# JadePlus_v0_3_1_schematics_PG1_ESP32S3.net
KiCad netlist of a schematic drawn in Altium Designer
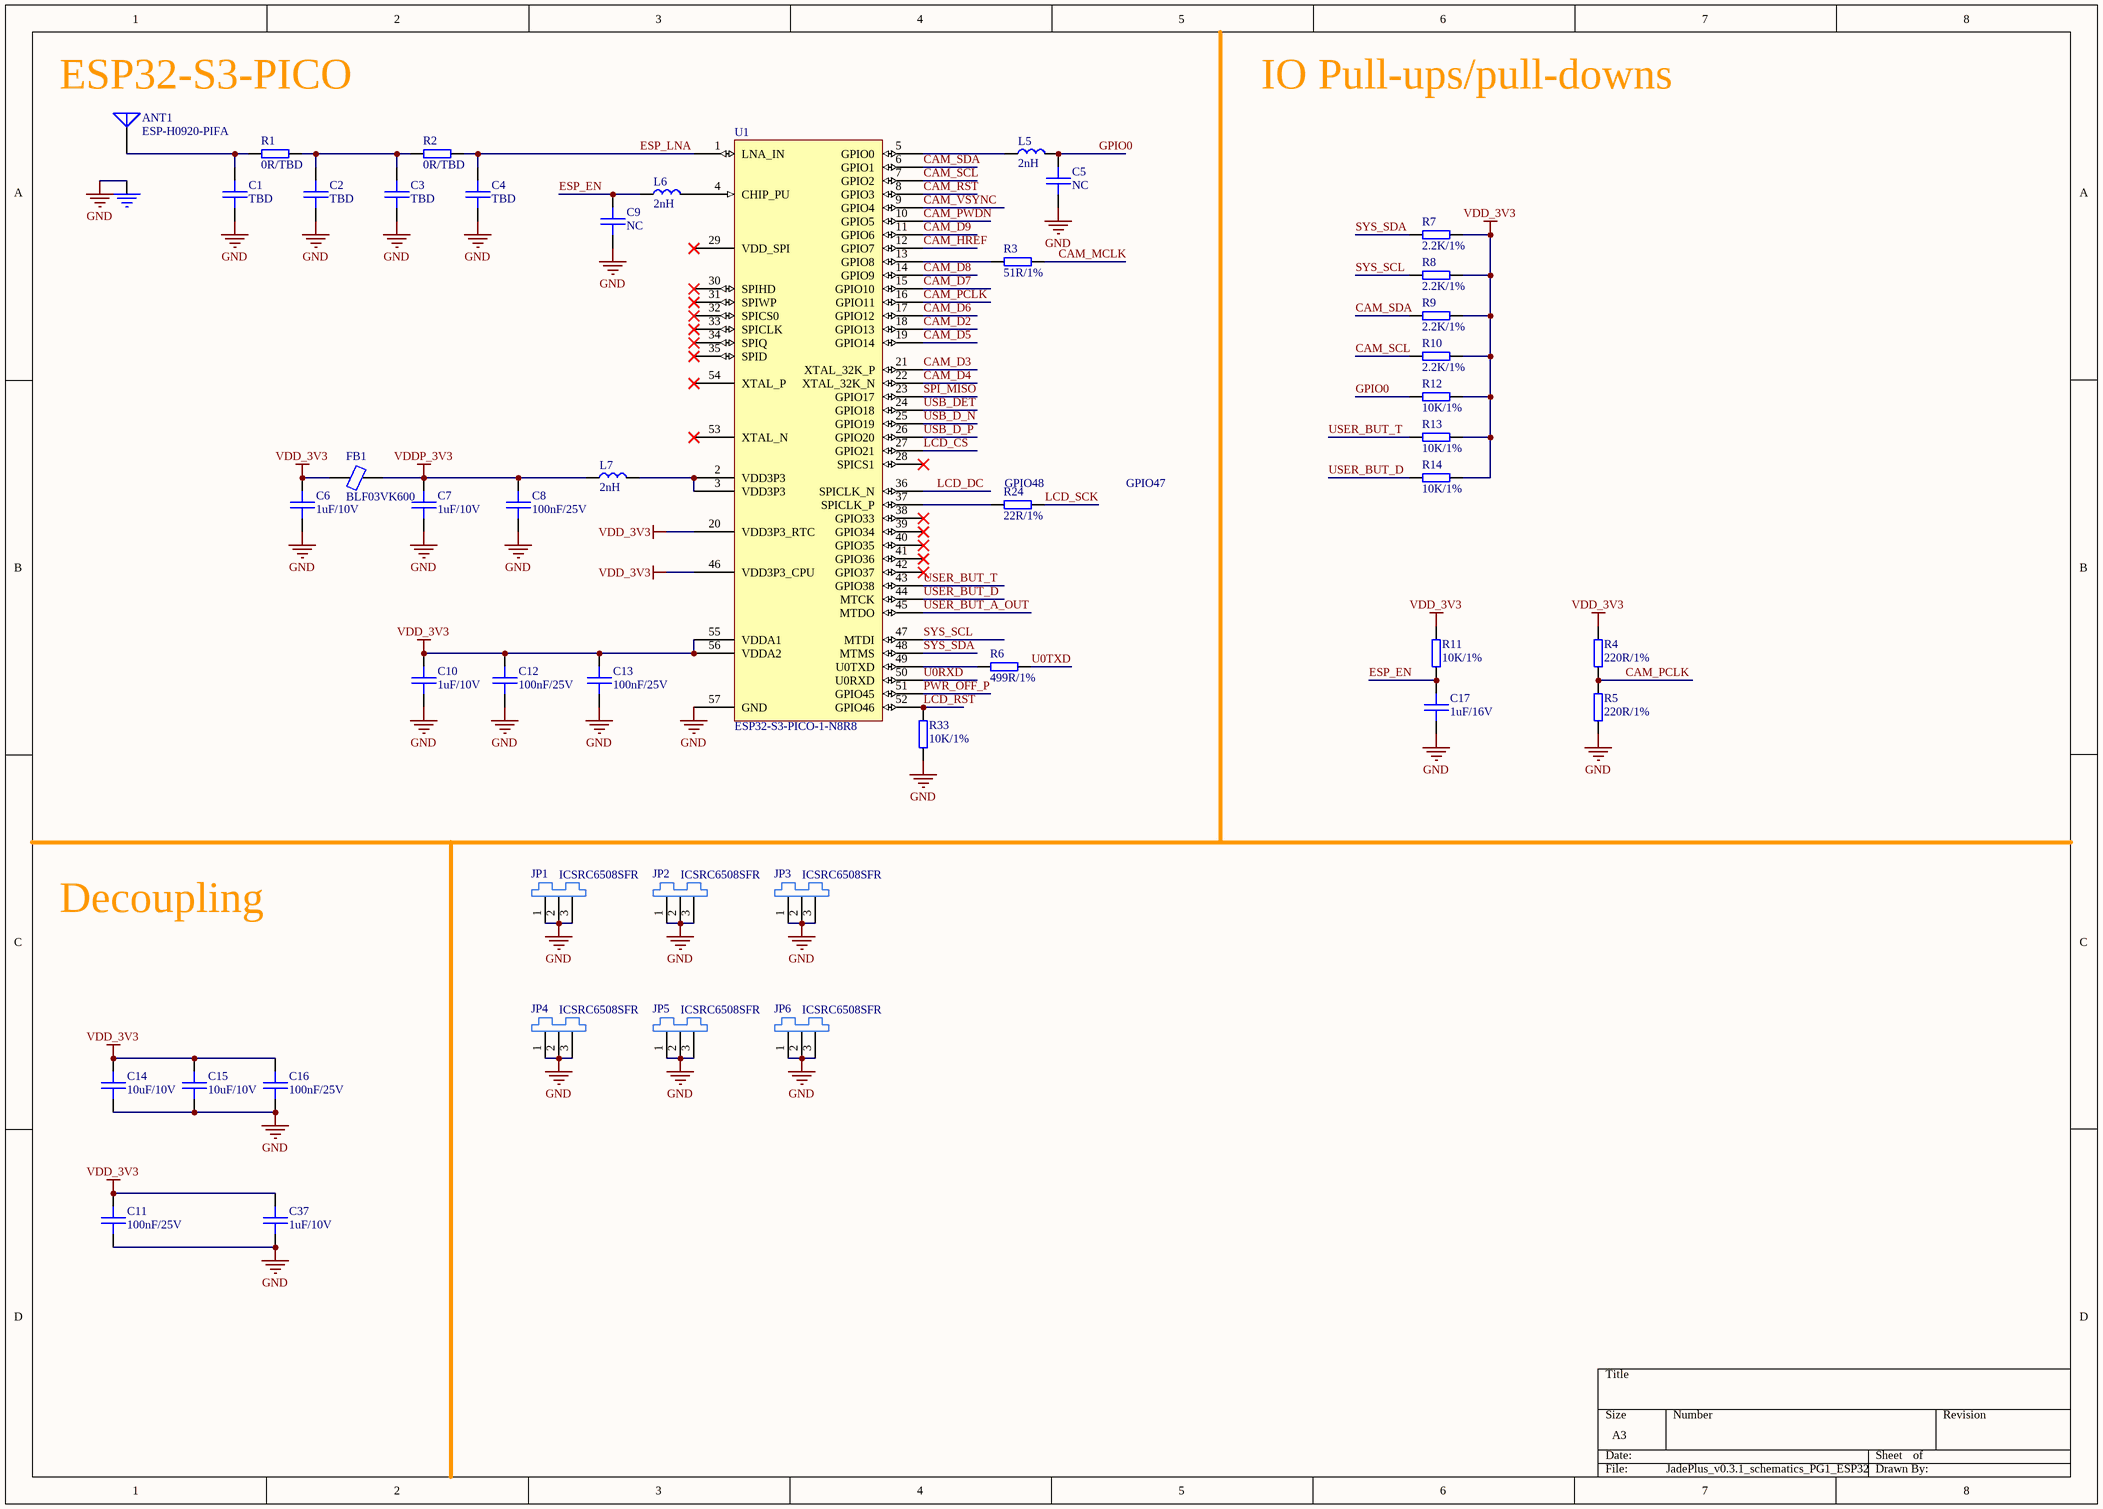
[diagram p0: JadePlus_v0.3.1_schematics_PG1_ESP32S3.SchDoc]

(export (version "E")
  (design (tool "Eeschema 10.0.6"))
  (components
    (comp (ref "ANT1")
      (value "ESP-H0920-PIFA")
      (footprint "ESP-H0920-PIFA")
      (description "Meandered Inverted F Antenna")
      (libsource (lib "Vowstar_Antenna") (part "Antenna_MIFA"))
    )
    (comp (ref "C1")
      (value "TBD")
      (footprint "HD-Components:C0201-HD")
      (description "Surface mount capacitor 0402")
      (libsource (lib "Vowstar_Basic_Device") (part "SMT_C_0402"))
    )
    (comp (ref "C2")
      (value "TBD")
      (footprint "HD-Components:C0201-HD")
      (description "Surface mount capacitor 0402")
      (libsource (lib "Vowstar_Basic_Device") (part "SMT_C_0402"))
    )
    (comp (ref "C3")
      (value "TBD")
      (footprint "HD-Components:C0201-HD")
      (description "Surface mount capacitor 0402")
      (libsource (lib "Vowstar_Basic_Device") (part "SMT_C_0402"))
    )
    (comp (ref "C4")
      (value "TBD")
      (footprint "HD-Components:C0201-HD")
      (description "Surface mount capacitor 0402")
      (libsource (lib "Vowstar_Basic_Device") (part "SMT_C_0402"))
    )
    (comp (ref "C5")
      (value "NC")
      (footprint "HD-Components:C0201-HD")
      (description "Surface mount capacitor 0402")
      (libsource (lib "Vowstar_Basic_Device") (part "SMT_C_0402"))
    )
    (comp (ref "C6")
      (value "1uF/10V")
      (footprint "HD-Components:C0201-HD")
      (description "Surface mount capacitor 0402")
      (libsource (lib "Vowstar_Basic_Device") (part "SMT_C_0402"))
    )
    (comp (ref "C7")
      (value "1uF/10V")
      (footprint "HD-Components:C0201-HD")
      (description "Surface mount capacitor 0402")
      (libsource (lib "Vowstar_Basic_Device") (part "SMT_C_0402"))
    )
    (comp (ref "C8")
      (value "100nF/25V")
      (footprint "HD-Components:C0201-HD")
      (description "Surface mount capacitor 0402")
      (libsource (lib "Vowstar_Basic_Device") (part "SMT_C_0402"))
    )
    (comp (ref "C9")
      (value "NC")
      (footprint "HD-Components:C0201-HD")
      (description "Surface mount capacitor 0402")
      (libsource (lib "Vowstar_Basic_Device") (part "SMT_C_0402"))
    )
    (comp (ref "C10")
      (value "1uF/10V")
      (footprint "HD-Components:C0201-HD")
      (description "Surface mount capacitor 0402")
      (libsource (lib "Vowstar_Basic_Device") (part "SMT_C_0402"))
    )
    (comp (ref "C11")
      (value "100nF/25V")
      (footprint "HD-Components:C0201-HD")
      (description "Surface mount capacitor 0402")
      (libsource (lib "Vowstar_Basic_Device") (part "SMT_C_0402"))
    )
    (comp (ref "C12")
      (value "100nF/25V")
      (footprint "HD-Components:C0201-HD")
      (description "Surface mount capacitor 0402")
      (libsource (lib "Vowstar_Basic_Device") (part "SMT_C_0402"))
    )
    (comp (ref "C13")
      (value "100nF/25V")
      (footprint "HD-Components:C0201-HD")
      (description "Surface mount capacitor 0402")
      (libsource (lib "Vowstar_Basic_Device") (part "SMT_C_0402"))
    )
    (comp (ref "C14")
      (value "10uF/10V")
      (footprint "HD-Components:C0402-L-HD")
      (description "Surface mount capacitor 0402")
      (libsource (lib "Vowstar_Basic_Device") (part "SMT_C_0402"))
    )
    (comp (ref "C15")
      (value "10uF/10V")
      (footprint "HD-Components:C0402-L-HD")
      (description "Surface mount capacitor 0402")
      (libsource (lib "Vowstar_Basic_Device") (part "SMT_C_0402"))
    )
    (comp (ref "C16")
      (value "100nF/25V")
      (footprint "HD-Components:C0201-HD")
      (description "Surface mount capacitor 0402")
      (libsource (lib "Vowstar_Basic_Device") (part "SMT_C_0402"))
    )
    (comp (ref "C17")
      (value "1uF/16V")
      (footprint "C0402-HD")
      (description "Surface mount capacitor 0402")
      (libsource (lib "Vowstar_Basic_Device") (part "SMT_C_0402"))
    )
    (comp (ref "C37")
      (value "1uF/10V")
      (footprint "HD-Components:C0201-HD")
      (description "Surface mount capacitor 0402")
      (libsource (lib "Vowstar_Basic_Device") (part "SMT_C_0402"))
    )
    (comp (ref "FB1")
      (value "BLF03VK600")
      (footprint "L0201-HD")
      (description "C1857815")
      (libsource (lib "Vowstar_Basic_Device") (part "SMT_FB_0402"))
    )
    (comp (ref "JP1")
      (value "ICSRC6508SFR")
      (footprint "PcbLib1:SMD_3P-L6.7-W0.9-R3-P2.65-ICSRC6508SFR")
      (libsource (lib "Schlib1") (part "ICSRC6508SFR"))
    )
    (comp (ref "JP2")
      (value "ICSRC6508SFR")
      (footprint "PcbLib1:SMD_3P-L6.7-W0.9-R3-P2.65-ICSRC6508SFR")
      (libsource (lib "Schlib1") (part "ICSRC6508SFR"))
    )
    (comp (ref "JP3")
      (value "ICSRC6508SFR")
      (footprint "PcbLib1:SMD_3P-L6.7-W0.9-R3-P2.65-ICSRC6508SFR")
      (libsource (lib "Schlib1") (part "ICSRC6508SFR"))
    )
    (comp (ref "JP4")
      (value "ICSRC6508SFR")
      (footprint "PcbLib1:SMD_3P-L6.7-W0.9-R3-P2.65-ICSRC6508SFR")
      (libsource (lib "Schlib1") (part "ICSRC6508SFR"))
    )
    (comp (ref "JP5")
      (value "ICSRC6508SFR")
      (footprint "PcbLib1:SMD_3P-L6.7-W0.9-R3-P2.65-ICSRC6508SFR")
      (libsource (lib "Schlib1") (part "ICSRC6508SFR"))
    )
    (comp (ref "JP6")
      (value "ICSRC6508SFR")
      (footprint "PcbLib1:SMD_3P-L6.7-W0.9-R3-P2.65-ICSRC6508SFR")
      (libsource (lib "Schlib1") (part "ICSRC6508SFR"))
    )
    (comp (ref "L5")
      (value "2nH")
      (footprint "L0201-HD")
      (description "Surface mount inductor 0201")
      (libsource (lib "Vowstar_Basic_Device") (part "SMT_L_0201"))
    )
    (comp (ref "L6")
      (value "2nH")
      (footprint "L0201-HD")
      (description "Surface mount inductor 0201")
      (libsource (lib "Vowstar_Basic_Device") (part "SMT_L_0201"))
    )
    (comp (ref "L7")
      (value "2nH")
      (footprint "L0201-HD")
      (description "Surface mount inductor 0201")
      (libsource (lib "Vowstar_Basic_Device") (part "SMT_L_0201"))
    )
    (comp (ref "R1")
      (value "0R/TBD")
      (footprint "HD-Components:C0201-HD")
      (description "Surface mount resistor 0402")
      (libsource (lib "Vowstar_Basic_Device") (part "SMT_R_0402"))
    )
    (comp (ref "R2")
      (value "0R/TBD")
      (footprint "HD-Components:C0201-HD")
      (description "Surface mount resistor 0402")
      (libsource (lib "Vowstar_Basic_Device") (part "SMT_R_0402"))
    )
    (comp (ref "R3")
      (value "51R/1%")
      (footprint "R0402-HD")
      (description "Surface mount resistor 0402")
      (libsource (lib "Vowstar_Basic_Device") (part "SMT_R_0402"))
    )
    (comp (ref "R4")
      (value "220R/1%")
      (footprint "R0402-HD")
      (description "Surface mount resistor 0402")
      (libsource (lib "Vowstar_Basic_Device") (part "SMT_R_0402"))
    )
    (comp (ref "R5")
      (value "220R/1%")
      (footprint "R0402-HD")
      (description "Surface mount resistor 0402")
      (libsource (lib "Vowstar_Basic_Device") (part "SMT_R_0402"))
    )
    (comp (ref "R6")
      (value "499R/1%")
      (footprint "R0402-HD")
      (description "Surface mount resistor 0402")
      (libsource (lib "Vowstar_Basic_Device") (part "SMT_R_0402"))
    )
    (comp (ref "R7")
      (value "2.2K/1%")
      (footprint "R0402-HD")
      (description "Surface mount resistor 0402")
      (libsource (lib "Vowstar_Basic_Device") (part "SMT_R_0402"))
    )
    (comp (ref "R8")
      (value "2.2K/1%")
      (footprint "R0402-HD")
      (description "Surface mount resistor 0402")
      (libsource (lib "Vowstar_Basic_Device") (part "SMT_R_0402"))
    )
    (comp (ref "R9")
      (value "2.2K/1%")
      (footprint "R0402-HD")
      (description "Surface mount resistor 0402")
      (libsource (lib "Vowstar_Basic_Device") (part "SMT_R_0402"))
    )
    (comp (ref "R10")
      (value "2.2K/1%")
      (footprint "R0402-HD")
      (description "Surface mount resistor 0402")
      (libsource (lib "Vowstar_Basic_Device") (part "SMT_R_0402"))
    )
    (comp (ref "R11")
      (value "10K/1%")
      (footprint "R0402-HD")
      (description "Surface mount resistor 0402")
      (libsource (lib "Vowstar_Basic_Device") (part "SMT_R_0402"))
    )
    (comp (ref "R12")
      (value "10K/1%")
      (footprint "R0402-HD")
      (description "Surface mount resistor 0402")
      (libsource (lib "Vowstar_Basic_Device") (part "SMT_R_0402"))
    )
    (comp (ref "R13")
      (value "10K/1%")
      (footprint "R0402-HD")
      (description "Surface mount resistor 0402")
      (libsource (lib "Vowstar_Basic_Device") (part "SMT_R_0402"))
    )
    (comp (ref "R14")
      (value "10K/1%")
      (footprint "R0402-HD")
      (description "Surface mount resistor 0402")
      (libsource (lib "Vowstar_Basic_Device") (part "SMT_R_0402"))
    )
    (comp (ref "R24")
      (value "22R/1%")
      (footprint "R0402-HD")
      (description "Surface mount resistor 0402")
      (libsource (lib "Vowstar_Basic_Device") (part "SMT_R_0402"))
    )
    (comp (ref "R33")
      (value "10K/1%")
      (footprint "R0402-HD")
      (description "Surface mount resistor 0402")
      (libsource (lib "Vowstar_Basic_Device") (part "SMT_R_0402"))
    )
    (comp (ref "U1")
      (value "ESP32-S3-PICO-1-N8R8")
      (footprint "xQFN_LIB:QFN40P700X700X90_HS-57N")
      (libsource (lib "Espressif-CHIP") (part "ESP32-S3"))
    )
  )
  (nets
    (net (code "1") (name "/CAM_D2") (class "Default")
      (node (ref "U1") (pin "18") (pinfunction "GPIO13_18") (pintype "bidirectional"))
    )
    (net (code "2") (name "/CAM_D3") (class "Default")
      (node (ref "U1") (pin "21") (pinfunction "XTAL_32K_P_21") (pintype "bidirectional"))
    )
    (net (code "3") (name "/CAM_D4") (class "Default")
      (node (ref "U1") (pin "22") (pinfunction "XTAL_32K_N_22") (pintype "bidirectional"))
    )
    (net (code "4") (name "/CAM_D5") (class "Default")
      (node (ref "U1") (pin "19") (pinfunction "GPIO14_19") (pintype "bidirectional"))
    )
    (net (code "5") (name "/CAM_D6") (class "Default")
      (node (ref "U1") (pin "17") (pinfunction "GPIO12_17") (pintype "bidirectional"))
    )
    (net (code "6") (name "/CAM_D7") (class "Default")
      (node (ref "U1") (pin "15") (pinfunction "GPIO10_15") (pintype "bidirectional"))
    )
    (net (code "7") (name "/CAM_D8") (class "Default")
      (node (ref "U1") (pin "14") (pinfunction "GPIO9_14") (pintype "bidirectional"))
    )
    (net (code "8") (name "/CAM_D9") (class "Default")
      (node (ref "U1") (pin "11") (pinfunction "GPIO6_11") (pintype "bidirectional"))
    )
    (net (code "9") (name "/CAM_HREF") (class "Default")
      (node (ref "U1") (pin "12") (pinfunction "GPIO7_12") (pintype "bidirectional"))
    )
    (net (code "10") (name "/CAM_MCLK") (class "Default")
      (node (ref "R3") (pin "1") (pinfunction "1_1") (pintype "passive"))
    )
    (net (code "11") (name "/CAM_PCLK") (class "Default")
      (node (ref "R4") (pin "2") (pinfunction "2_2") (pintype "passive"))
      (node (ref "R5") (pin "1") (pinfunction "1_1") (pintype "passive"))
      (node (ref "U1") (pin "16") (pinfunction "GPIO11_16") (pintype "bidirectional"))
    )
    (net (code "12") (name "/CAM_PWDN") (class "Default")
      (node (ref "U1") (pin "10") (pinfunction "GPIO5_10") (pintype "bidirectional"))
    )
    (net (code "13") (name "/CAM_RST") (class "Default")
      (node (ref "U1") (pin "8") (pinfunction "GPIO3_8") (pintype "bidirectional"))
    )
    (net (code "14") (name "/CAM_SCL") (class "Default")
      (node (ref "R10") (pin "1") (pinfunction "1_1") (pintype "passive"))
      (node (ref "U1") (pin "7") (pinfunction "GPIO2_7") (pintype "bidirectional"))
    )
    (net (code "15") (name "/CAM_SDA") (class "Default")
      (node (ref "R9") (pin "1") (pinfunction "1_1") (pintype "passive"))
      (node (ref "U1") (pin "6") (pinfunction "GPIO1_6") (pintype "bidirectional"))
    )
    (net (code "16") (name "/CAM_VSYNC") (class "Default")
      (node (ref "U1") (pin "9") (pinfunction "GPIO4_9") (pintype "bidirectional"))
    )
    (net (code "17") (name "/ESP_EN") (class "Default")
      (node (ref "C17") (pin "2") (pinfunction "2_2") (pintype "passive"))
      (node (ref "C9") (pin "1") (pinfunction "1_1") (pintype "passive"))
      (node (ref "L6") (pin "2") (pinfunction "2_2") (pintype "passive"))
      (node (ref "R11") (pin "2") (pinfunction "2_2") (pintype "passive"))
    )
    (net (code "18") (name "/ESP_LNA") (class "Default")
      (node (ref "C4") (pin "2") (pinfunction "2_2") (pintype "passive"))
      (node (ref "R2") (pin "2") (pinfunction "2_2") (pintype "passive"))
      (node (ref "U1") (pin "1") (pinfunction "LNA_IN_1") (pintype "bidirectional"))
    )
    (net (code "19") (name "/GPIO0") (class "Default")
      (node (ref "C5") (pin "1") (pinfunction "1_1") (pintype "passive"))
      (node (ref "L5") (pin "1") (pinfunction "1_1") (pintype "passive"))
      (node (ref "R12") (pin "1") (pinfunction "1_1") (pintype "passive"))
    )
    (net (code "20") (name "/LCD_CS") (class "Default")
      (node (ref "U1") (pin "27") (pinfunction "GPIO21_27") (pintype "bidirectional"))
    )
    (net (code "21") (name "/LCD_DC") (class "Default")
      (node (ref "U1") (pin "36") (pinfunction "SPICLK_N_36") (pintype "bidirectional"))
    )
    (net (code "22") (name "/LCD_RST") (class "Default")
      (node (ref "R33") (pin "2") (pinfunction "2_2") (pintype "passive"))
      (node (ref "U1") (pin "52") (pinfunction "GPIO46_52") (pintype "bidirectional"))
    )
    (net (code "23") (name "/LCD_SCK") (class "Default")
      (node (ref "R24") (pin "1") (pinfunction "1_1") (pintype "passive"))
    )
    (net (code "24") (name "/PWR_OFF_P") (class "Default")
      (node (ref "U1") (pin "51") (pinfunction "GPIO45_51") (pintype "bidirectional"))
    )
    (net (code "25") (name "/SPI_MISO") (class "Default")
      (node (ref "U1") (pin "23") (pinfunction "GPIO17_23") (pintype "bidirectional"))
    )
    (net (code "26") (name "/SYS_SCL") (class "Default")
      (node (ref "R8") (pin "1") (pinfunction "1_1") (pintype "passive"))
      (node (ref "U1") (pin "47") (pinfunction "MTDI_47") (pintype "bidirectional"))
    )
    (net (code "27") (name "/SYS_SDA") (class "Default")
      (node (ref "R7") (pin "1") (pinfunction "1_1") (pintype "passive"))
      (node (ref "U1") (pin "48") (pinfunction "MTMS_48") (pintype "bidirectional"))
    )
    (net (code "28") (name "/U0RXD") (class "Default")
      (node (ref "U1") (pin "50") (pinfunction "U0RXD_50") (pintype "bidirectional"))
    )
    (net (code "29") (name "/U0TXD") (class "Default")
      (node (ref "R6") (pin "1") (pinfunction "1_1") (pintype "passive"))
    )
    (net (code "30") (name "/USB_DET") (class "Default")
      (node (ref "U1") (pin "24") (pinfunction "GPIO18_24") (pintype "bidirectional"))
    )
    (net (code "31") (name "/USB_D_N") (class "Default")
      (node (ref "U1") (pin "25") (pinfunction "GPIO19_25") (pintype "bidirectional"))
    )
    (net (code "32") (name "/USB_D_P") (class "Default")
      (node (ref "U1") (pin "26") (pinfunction "GPIO20_26") (pintype "bidirectional"))
    )
    (net (code "33") (name "/USER_BUT_A_OUT") (class "Default")
      (node (ref "U1") (pin "45") (pinfunction "MTDO_45") (pintype "bidirectional"))
    )
    (net (code "34") (name "/USER_BUT_D") (class "Default")
      (node (ref "R14") (pin "1") (pinfunction "1_1") (pintype "passive"))
      (node (ref "U1") (pin "44") (pinfunction "MTCK_44") (pintype "bidirectional"))
    )
    (net (code "35") (name "/USER_BUT_T") (class "Default")
      (node (ref "R13") (pin "1") (pinfunction "1_1") (pintype "passive"))
      (node (ref "U1") (pin "43") (pinfunction "GPIO38_43") (pintype "bidirectional"))
    )
    (net (code "36") (name "GND") (class "Default")
      (node (ref "ANT1") (pin "2") (pinfunction "G_2") (pintype "passive"))
      (node (ref "C1") (pin "1") (pinfunction "1_1") (pintype "passive"))
      (node (ref "C10") (pin "2") (pinfunction "2_2") (pintype "passive"))
      (node (ref "C11") (pin "2") (pinfunction "2_2") (pintype "passive"))
      (node (ref "C12") (pin "2") (pinfunction "2_2") (pintype "passive"))
      (node (ref "C13") (pin "2") (pinfunction "2_2") (pintype "passive"))
      (node (ref "C14") (pin "1") (pinfunction "1_1") (pintype "passive"))
      (node (ref "C15") (pin "1") (pinfunction "1_1") (pintype "passive"))
      (node (ref "C16") (pin "2") (pinfunction "2_2") (pintype "passive"))
      (node (ref "C17") (pin "1") (pinfunction "1_1") (pintype "passive"))
      (node (ref "C2") (pin "1") (pinfunction "1_1") (pintype "passive"))
      (node (ref "C3") (pin "1") (pinfunction "1_1") (pintype "passive"))
      (node (ref "C37") (pin "2") (pinfunction "2_2") (pintype "passive"))
      (node (ref "C4") (pin "1") (pinfunction "1_1") (pintype "passive"))
      (node (ref "C5") (pin "2") (pinfunction "2_2") (pintype "passive"))
      (node (ref "C6") (pin "2") (pinfunction "2_2") (pintype "passive"))
      (node (ref "C7") (pin "1") (pinfunction "1_1") (pintype "passive"))
      (node (ref "C8") (pin "2") (pinfunction "2_2") (pintype "passive"))
      (node (ref "C9") (pin "2") (pinfunction "2_2") (pintype "passive"))
      (node (ref "JP1") (pin "1") (pinfunction "GND_1") (pintype "passive"))
      (node (ref "JP1") (pin "2") (pinfunction "GND_2") (pintype "passive"))
      (node (ref "JP1") (pin "3") (pinfunction "GND_3") (pintype "passive"))
      (node (ref "JP2") (pin "1") (pinfunction "GND_1") (pintype "passive"))
      (node (ref "JP2") (pin "2") (pinfunction "GND_2") (pintype "passive"))
      (node (ref "JP2") (pin "3") (pinfunction "GND_3") (pintype "passive"))
      (node (ref "JP3") (pin "1") (pinfunction "GND_1") (pintype "passive"))
      (node (ref "JP3") (pin "2") (pinfunction "GND_2") (pintype "passive"))
      (node (ref "JP3") (pin "3") (pinfunction "GND_3") (pintype "passive"))
      (node (ref "JP4") (pin "1") (pinfunction "GND_1") (pintype "passive"))
      (node (ref "JP4") (pin "2") (pinfunction "GND_2") (pintype "passive"))
      (node (ref "JP4") (pin "3") (pinfunction "GND_3") (pintype "passive"))
      (node (ref "JP5") (pin "1") (pinfunction "GND_1") (pintype "passive"))
      (node (ref "JP5") (pin "2") (pinfunction "GND_2") (pintype "passive"))
      (node (ref "JP5") (pin "3") (pinfunction "GND_3") (pintype "passive"))
      (node (ref "JP6") (pin "1") (pinfunction "GND_1") (pintype "passive"))
      (node (ref "JP6") (pin "2") (pinfunction "GND_2") (pintype "passive"))
      (node (ref "JP6") (pin "3") (pinfunction "GND_3") (pintype "passive"))
      (node (ref "R33") (pin "1") (pinfunction "1_1") (pintype "passive"))
      (node (ref "R5") (pin "2") (pinfunction "2_2") (pintype "passive"))
      (node (ref "U1") (pin "57") (pinfunction "GND_57") (pintype "power_in"))
    )
    (net (code "37") (name "Net-(ANT1-A)") (class "Default")
      (node (ref "ANT1") (pin "1") (pinfunction "A_1") (pintype "passive"))
      (node (ref "C1") (pin "2") (pinfunction "2_2") (pintype "passive"))
      (node (ref "R1") (pin "1") (pinfunction "1_1") (pintype "passive"))
    )
    (net (code "38") (name "Net-(C2-Pad2)") (class "Default")
      (node (ref "C2") (pin "2") (pinfunction "2_2") (pintype "passive"))
      (node (ref "C3") (pin "2") (pinfunction "2_2") (pintype "passive"))
      (node (ref "R1") (pin "2") (pinfunction "2_2") (pintype "passive"))
      (node (ref "R2") (pin "1") (pinfunction "1_1") (pintype "passive"))
    )
    (net (code "39") (name "Net-(L7-Pad1)") (class "Default")
      (node (ref "L7") (pin "1") (pinfunction "1_1") (pintype "passive"))
      (node (ref "U1") (pin "2") (pinfunction "VDD3P3_2") (pintype "power_in"))
      (node (ref "U1") (pin "3") (pinfunction "VDD3P3_3") (pintype "power_in"))
    )
    (net (code "40") (name "Net-(U1-CHIP_PU)") (class "Default")
      (node (ref "L6") (pin "1") (pinfunction "1_1") (pintype "passive"))
      (node (ref "U1") (pin "4") (pinfunction "CHIP_PU_4") (pintype "input"))
    )
    (net (code "41") (name "Net-(U1-GPIO0)") (class "Default")
      (node (ref "L5") (pin "2") (pinfunction "2_2") (pintype "passive"))
      (node (ref "U1") (pin "5") (pinfunction "GPIO0_5") (pintype "bidirectional"))
    )
    (net (code "42") (name "Net-(U1-GPIO8)") (class "Default")
      (node (ref "R3") (pin "2") (pinfunction "2_2") (pintype "passive"))
      (node (ref "U1") (pin "13") (pinfunction "GPIO8_13") (pintype "bidirectional"))
    )
    (net (code "43") (name "Net-(U1-SPICLK_P)") (class "Default")
      (node (ref "R24") (pin "2") (pinfunction "2_2") (pintype "passive"))
      (node (ref "U1") (pin "37") (pinfunction "SPICLK_P_37") (pintype "bidirectional"))
    )
    (net (code "44") (name "Net-(U1-U0TXD)") (class "Default")
      (node (ref "R6") (pin "2") (pinfunction "2_2") (pintype "passive"))
      (node (ref "U1") (pin "49") (pinfunction "U0TXD_49") (pintype "bidirectional"))
    )
    (net (code "45") (name "VDDP_3V3") (class "Default")
      (node (ref "C7") (pin "2") (pinfunction "2_2") (pintype "passive"))
      (node (ref "C8") (pin "1") (pinfunction "1_1") (pintype "passive"))
      (node (ref "FB1") (pin "1") (pinfunction "1_1") (pintype "passive"))
      (node (ref "L7") (pin "2") (pinfunction "2_2") (pintype "passive"))
    )
    (net (code "46") (name "VDD_3V3") (class "Default")
      (node (ref "C10") (pin "1") (pinfunction "1_1") (pintype "passive"))
      (node (ref "C11") (pin "1") (pinfunction "1_1") (pintype "passive"))
      (node (ref "C12") (pin "1") (pinfunction "1_1") (pintype "passive"))
      (node (ref "C13") (pin "1") (pinfunction "1_1") (pintype "passive"))
      (node (ref "C14") (pin "2") (pinfunction "2_2") (pintype "passive"))
      (node (ref "C15") (pin "2") (pinfunction "2_2") (pintype "passive"))
      (node (ref "C16") (pin "1") (pinfunction "1_1") (pintype "passive"))
      (node (ref "C37") (pin "1") (pinfunction "1_1") (pintype "passive"))
      (node (ref "C6") (pin "1") (pinfunction "1_1") (pintype "passive"))
      (node (ref "FB1") (pin "2") (pinfunction "2_2") (pintype "passive"))
      (node (ref "R10") (pin "2") (pinfunction "2_2") (pintype "passive"))
      (node (ref "R11") (pin "1") (pinfunction "1_1") (pintype "passive"))
      (node (ref "R12") (pin "2") (pinfunction "2_2") (pintype "passive"))
      (node (ref "R13") (pin "2") (pinfunction "2_2") (pintype "passive"))
      (node (ref "R14") (pin "2") (pinfunction "2_2") (pintype "passive"))
      (node (ref "R4") (pin "1") (pinfunction "1_1") (pintype "passive"))
      (node (ref "R7") (pin "2") (pinfunction "2_2") (pintype "passive"))
      (node (ref "R8") (pin "2") (pinfunction "2_2") (pintype "passive"))
      (node (ref "R9") (pin "2") (pinfunction "2_2") (pintype "passive"))
      (node (ref "U1") (pin "20") (pinfunction "VDD3P3_RTC_20") (pintype "power_in"))
      (node (ref "U1") (pin "46") (pinfunction "VDD3P3_CPU_46") (pintype "power_in"))
      (node (ref "U1") (pin "55") (pinfunction "VDDA1_55") (pintype "power_in"))
      (node (ref "U1") (pin "56") (pinfunction "VDDA2_56") (pintype "power_in"))
    )
    (net (code "47") (name "unconnected-(U1-GPIO33-Pad38)") (class "Default")
      (node (ref "U1") (pin "38") (pinfunction "GPIO33_38") (pintype "bidirectional+no_connect"))
    )
    (net (code "48") (name "unconnected-(U1-GPIO34-Pad39)") (class "Default")
      (node (ref "U1") (pin "39") (pinfunction "GPIO34_39") (pintype "bidirectional+no_connect"))
    )
    (net (code "49") (name "unconnected-(U1-GPIO35-Pad40)") (class "Default")
      (node (ref "U1") (pin "40") (pinfunction "GPIO35_40") (pintype "bidirectional+no_connect"))
    )
    (net (code "50") (name "unconnected-(U1-GPIO36-Pad41)") (class "Default")
      (node (ref "U1") (pin "41") (pinfunction "GPIO36_41") (pintype "bidirectional+no_connect"))
    )
    (net (code "51") (name "unconnected-(U1-GPIO37-Pad42)") (class "Default")
      (node (ref "U1") (pin "42") (pinfunction "GPIO37_42") (pintype "bidirectional+no_connect"))
    )
    (net (code "52") (name "unconnected-(U1-SPICLK-Pad33)") (class "Default")
      (node (ref "U1") (pin "33") (pinfunction "SPICLK_33") (pintype "bidirectional+no_connect"))
    )
    (net (code "53") (name "unconnected-(U1-SPICS0-Pad32)") (class "Default")
      (node (ref "U1") (pin "32") (pinfunction "SPICS0_32") (pintype "bidirectional+no_connect"))
    )
    (net (code "54") (name "unconnected-(U1-SPICS1-Pad28)") (class "Default")
      (node (ref "U1") (pin "28") (pinfunction "SPICS1_28") (pintype "bidirectional+no_connect"))
    )
    (net (code "55") (name "unconnected-(U1-SPID-Pad35)") (class "Default")
      (node (ref "U1") (pin "35") (pinfunction "SPID_35") (pintype "bidirectional+no_connect"))
    )
    (net (code "56") (name "unconnected-(U1-SPIHD-Pad30)") (class "Default")
      (node (ref "U1") (pin "30") (pinfunction "SPIHD_30") (pintype "bidirectional+no_connect"))
    )
    (net (code "57") (name "unconnected-(U1-SPIQ-Pad34)") (class "Default")
      (node (ref "U1") (pin "34") (pinfunction "SPIQ_34") (pintype "bidirectional+no_connect"))
    )
    (net (code "58") (name "unconnected-(U1-SPIWP-Pad31)") (class "Default")
      (node (ref "U1") (pin "31") (pinfunction "SPIWP_31") (pintype "bidirectional+no_connect"))
    )
    (net (code "59") (name "unconnected-(U1-VDD_SPI-Pad29)") (class "Default")
      (node (ref "U1") (pin "29") (pinfunction "VDD_SPI_29") (pintype "power_in+no_connect"))
    )
    (net (code "60") (name "unconnected-(U1-XTAL_N-Pad53)") (class "Default")
      (node (ref "U1") (pin "53") (pinfunction "XTAL_N_53") (pintype "passive+no_connect"))
    )
    (net (code "61") (name "unconnected-(U1-XTAL_P-Pad54)") (class "Default")
      (node (ref "U1") (pin "54") (pinfunction "XTAL_P_54") (pintype "passive+no_connect"))
    )
  )
)
